# adafruit_rgblcdshield.net
KiCad netlist of a schematic drawn in EAGLE
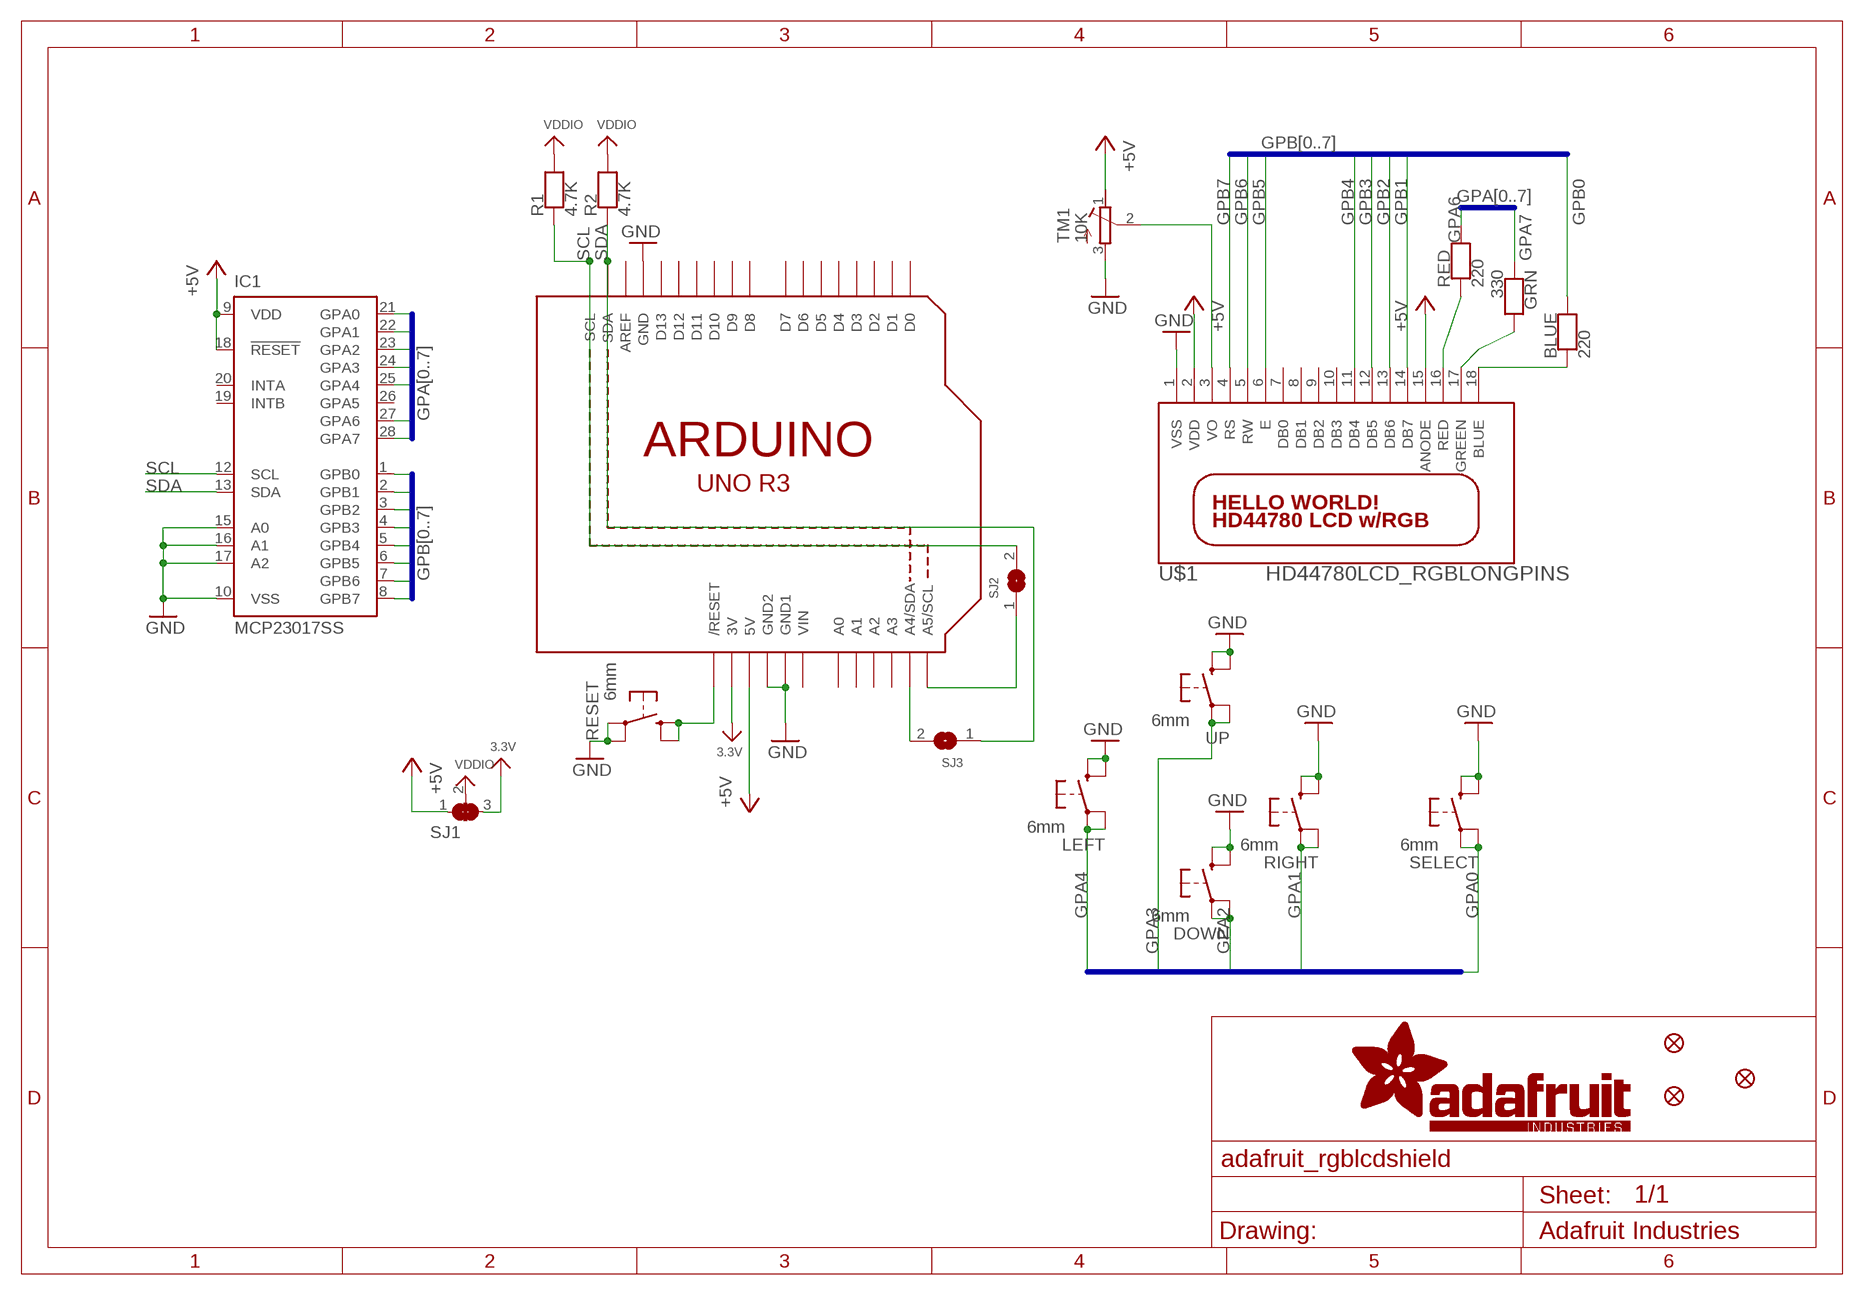
[diagram p0: schematic, sheet 1]

(export (version "E")
  (design (tool "Eeschema 10.0.6"))
  (components
    (comp (ref "BLUE")
      (value "220")
      (footprint "eagle-import:0805-NO")
      (libsource (lib "eagle-import") (part "RESISTOR0805_NOOUTLINE"))
    )
    (comp (ref "DOWN")
      (value "6mm")
      (footprint "eagle-import:6MMX6MM_TACTILE_SMT")
      (libsource (lib "eagle-import") (part "SWITCH_TACT_SMT_6MM"))
    )
    (comp (ref "FID1")
      (value "FIDUCIAL_1MM")
      (footprint "eagle-import:FIDUCIAL_1MM")
      (libsource (lib "eagle-import") (part "FIDUCIAL_1MM"))
    )
    (comp (ref "FID2")
      (value "FIDUCIAL_1MM")
      (footprint "eagle-import:FIDUCIAL_1MM")
      (libsource (lib "eagle-import") (part "FIDUCIAL_1MM"))
    )
    (comp (ref "FID3")
      (value "FIDUCIAL_1MM")
      (footprint "eagle-import:FIDUCIAL_1MM")
      (libsource (lib "eagle-import") (part "FIDUCIAL_1MM"))
    )
    (comp (ref "GRN")
      (value "330")
      (footprint "eagle-import:0805-NO")
      (libsource (lib "eagle-import") (part "RESISTOR0805_NOOUTLINE"))
    )
    (comp (ref "IC1")
      (value "MCP23017SS")
      (footprint "eagle-import:SSOP28")
      (libsource (lib "eagle-import") (part "MCP23017SS"))
    )
    (comp (ref "LEFT")
      (value "6mm")
      (footprint "eagle-import:6MMX6MM_TACTILE_SMT")
      (libsource (lib "eagle-import") (part "SWITCH_TACT_SMT_6MM"))
    )
    (comp (ref "R1")
      (value "4.7K")
      (footprint "eagle-import:0805-NO")
      (libsource (lib "eagle-import") (part "RESISTOR0805_NOOUTLINE"))
    )
    (comp (ref "R2")
      (value "4.7K")
      (footprint "eagle-import:0805-NO")
      (libsource (lib "eagle-import") (part "RESISTOR0805_NOOUTLINE"))
    )
    (comp (ref "RED")
      (value "220")
      (footprint "eagle-import:0805-NO")
      (libsource (lib "eagle-import") (part "RESISTOR0805_NOOUTLINE"))
    )
    (comp (ref "RESET")
      (value "6mm")
      (footprint "eagle-import:6MMX6MM_TACTILE_SMT")
      (libsource (lib "eagle-import") (part "SWITCH_TACT_SMT_6MM"))
    )
    (comp (ref "RIGHT")
      (value "6mm")
      (footprint "eagle-import:6MMX6MM_TACTILE_SMT")
      (libsource (lib "eagle-import") (part "SWITCH_TACT_SMT_6MM"))
    )
    (comp (ref "SELECT")
      (value "6mm")
      (footprint "eagle-import:6MMX6MM_TACTILE_SMT")
      (libsource (lib "eagle-import") (part "SWITCH_TACT_SMT_6MM"))
    )
    (comp (ref "SJ1")
      (value "SOLDERJUMPER_2WAY")
      (footprint "eagle-import:SOLDERJUMPER_2WAY_OPEN_NOPASTE")
      (libsource (lib "eagle-import") (part "SOLDERJUMPER_2WAY"))
    )
    (comp (ref "SJ2")
      (value "SOLDERJUMPER")
      (footprint "eagle-import:SOLDERJUMPER_ARROW_NOPASTE")
      (libsource (lib "eagle-import") (part "SOLDERJUMPER"))
    )
    (comp (ref "SJ3")
      (value "SOLDERJUMPER")
      (footprint "eagle-import:SOLDERJUMPER_ARROW_NOPASTE")
      (libsource (lib "eagle-import") (part "SOLDERJUMPER"))
    )
    (comp (ref "TM1")
      (value "10K")
      (footprint "eagle-import:RTRIM3314J")
      (libsource (lib "eagle-import") (part "R-TRIMM3314J"))
    )
    (comp (ref "U$1")
      (value "HD44780LCD_RGBLONGPINS")
      (footprint "eagle-import:LCD1602-RGB")
      (libsource (lib "eagle-import") (part "HD44780LCD_RGBLONGPINS"))
    )
    (comp (ref "U1")
      (value "ARDUINOR3-NOIOREF-NOTEXT")
      (footprint "eagle-import:ARDUINOR3-NOTEXT-NOIOREF")
      (libsource (lib "eagle-import") (part "ARDUINOR3-NOIOREF-NOTEXT"))
    )
    (comp (ref "UP")
      (value "6mm")
      (footprint "eagle-import:6MMX6MM_TACTILE_SMT")
      (libsource (lib "eagle-import") (part "SWITCH_TACT_SMT_6MM"))
    )
  )
  (nets
    (net (code "2") (name "+5V") (class "Default")
      (node (ref "IC1") (pin "18") (pinfunction "~{RESET}_18") (pintype "input"))
      (node (ref "IC1") (pin "9") (pinfunction "VDD_9") (pintype "power_in"))
      (node (ref "SJ1") (pin "1") (pinfunction "1_1") (pintype "passive"))
      (node (ref "TM1") (pin "1") (pinfunction "E_1") (pintype "passive"))
      (node (ref "U$1") (pin "15") (pinfunction "ANODE_15") (pintype "input"))
      (node (ref "U$1") (pin "2") (pinfunction "VDD_2") (pintype "power_in"))
      (node (ref "U1") (pin "5V") (pinfunction "5V_5V") (pintype "power_in"))
    )
    (net (code "3") (name "/GPA0") (class "Default")
      (node (ref "IC1") (pin "21") (pinfunction "GPA0_21") (pintype "bidirectional"))
      (node (ref "SELECT") (pin "A") (pinfunction "P_A") (pintype "passive"))
      (node (ref "SELECT") (pin "A'") (pinfunction "P1_A'") (pintype "passive"))
    )
    (net (code "4") (name "/GPA1") (class "Default")
      (node (ref "IC1") (pin "22") (pinfunction "GPA1_22") (pintype "bidirectional"))
      (node (ref "RIGHT") (pin "A") (pinfunction "P_A") (pintype "passive"))
      (node (ref "RIGHT") (pin "A'") (pinfunction "P1_A'") (pintype "passive"))
    )
    (net (code "5") (name "/GPA2") (class "Default")
      (node (ref "DOWN") (pin "A") (pinfunction "P_A") (pintype "passive"))
      (node (ref "DOWN") (pin "A'") (pinfunction "P1_A'") (pintype "passive"))
      (node (ref "IC1") (pin "23") (pinfunction "GPA2_23") (pintype "bidirectional"))
    )
    (net (code "6") (name "/GPA3") (class "Default")
      (node (ref "IC1") (pin "24") (pinfunction "GPA3_24") (pintype "bidirectional"))
      (node (ref "UP") (pin "A") (pinfunction "P_A") (pintype "passive"))
      (node (ref "UP") (pin "A'") (pinfunction "P1_A'") (pintype "passive"))
    )
    (net (code "7") (name "/GPA4") (class "Default")
      (node (ref "IC1") (pin "25") (pinfunction "GPA4_25") (pintype "bidirectional"))
      (node (ref "LEFT") (pin "A") (pinfunction "P_A") (pintype "passive"))
      (node (ref "LEFT") (pin "A'") (pinfunction "P1_A'") (pintype "passive"))
    )
    (net (code "8") (name "/GPA6") (class "Default")
      (node (ref "IC1") (pin "27") (pinfunction "GPA6_27") (pintype "bidirectional"))
      (node (ref "RED") (pin "2") (pinfunction "2_2") (pintype "passive"))
    )
    (net (code "9") (name "/GPA7") (class "Default")
      (node (ref "GRN") (pin "1") (pinfunction "1_1") (pintype "passive"))
      (node (ref "IC1") (pin "28") (pinfunction "GPA7_28") (pintype "bidirectional"))
    )
    (net (code "11") (name "/GPB0") (class "Default")
      (node (ref "BLUE") (pin "2") (pinfunction "2_2") (pintype "passive"))
      (node (ref "IC1") (pin "1") (pinfunction "GPB0_1") (pintype "bidirectional"))
    )
    (net (code "12") (name "/GPB1") (class "Default")
      (node (ref "IC1") (pin "2") (pinfunction "GPB1_2") (pintype "bidirectional"))
      (node (ref "U$1") (pin "14") (pinfunction "DB7_14") (pintype "bidirectional"))
    )
    (net (code "13") (name "/GPB2") (class "Default")
      (node (ref "IC1") (pin "3") (pinfunction "GPB2_3") (pintype "bidirectional"))
      (node (ref "U$1") (pin "13") (pinfunction "DB6_13") (pintype "bidirectional"))
    )
    (net (code "14") (name "/GPB3") (class "Default")
      (node (ref "IC1") (pin "4") (pinfunction "GPB3_4") (pintype "bidirectional"))
      (node (ref "U$1") (pin "12") (pinfunction "DB5_12") (pintype "bidirectional"))
    )
    (net (code "15") (name "/GPB4") (class "Default")
      (node (ref "IC1") (pin "5") (pinfunction "GPB4_5") (pintype "bidirectional"))
      (node (ref "U$1") (pin "11") (pinfunction "DB4_11") (pintype "bidirectional"))
    )
    (net (code "16") (name "/GPB5") (class "Default")
      (node (ref "IC1") (pin "6") (pinfunction "GPB5_6") (pintype "bidirectional"))
      (node (ref "U$1") (pin "6") (pinfunction "E_6") (pintype "input"))
    )
    (net (code "17") (name "/GPB6") (class "Default")
      (node (ref "IC1") (pin "7") (pinfunction "GPB6_7") (pintype "bidirectional"))
      (node (ref "U$1") (pin "5") (pinfunction "RW_5") (pintype "input"))
    )
    (net (code "18") (name "/GPB7") (class "Default")
      (node (ref "IC1") (pin "8") (pinfunction "GPB7_8") (pintype "bidirectional"))
      (node (ref "U$1") (pin "4") (pinfunction "RS_4") (pintype "input"))
    )
    (net (code "20") (name "/SCL") (class "Default")
      (node (ref "IC1") (pin "12") (pinfunction "SCL_12") (pintype "input"))
      (node (ref "R1") (pin "1") (pinfunction "1_1") (pintype "passive"))
      (node (ref "SJ2") (pin "2") (pinfunction "2_2") (pintype "passive"))
      (node (ref "U1") (pin "SCL") (pinfunction "SCL_SCL") (pintype "bidirectional"))
    )
    (net (code "21") (name "/SDA") (class "Default")
      (node (ref "IC1") (pin "13") (pinfunction "SDA_13") (pintype "bidirectional"))
      (node (ref "R2") (pin "1") (pinfunction "1_1") (pintype "passive"))
      (node (ref "SJ3") (pin "1") (pinfunction "1_1") (pintype "passive"))
      (node (ref "U1") (pin "SDA") (pinfunction "SDA_SDA") (pintype "bidirectional"))
    )
    (net (code "22") (name "/VIN") (class "Default")
      (node (ref "U1") (pin "VIN") (pinfunction "VIN_VIN") (pintype "power_in"))
    )
    (net (code "23") (name "3.3V") (class "Default")
      (node (ref "SJ1") (pin "3") (pinfunction "3_3") (pintype "passive"))
      (node (ref "U1") (pin "3V") (pinfunction "3V_3V") (pintype "power_in"))
    )
    (net (code "24") (name "GND") (class "Default")
      (node (ref "DOWN") (pin "B") (pinfunction "S_B") (pintype "passive"))
      (node (ref "DOWN") (pin "B'") (pinfunction "S1_B'") (pintype "passive"))
      (node (ref "IC1") (pin "10") (pinfunction "VSS_10") (pintype "power_in"))
      (node (ref "IC1") (pin "15") (pinfunction "A0_15") (pintype "input"))
      (node (ref "IC1") (pin "16") (pinfunction "A1_16") (pintype "input"))
      (node (ref "IC1") (pin "17") (pinfunction "A2_17") (pintype "input"))
      (node (ref "LEFT") (pin "B") (pinfunction "S_B") (pintype "passive"))
      (node (ref "LEFT") (pin "B'") (pinfunction "S1_B'") (pintype "passive"))
      (node (ref "RESET") (pin "A") (pinfunction "P_A") (pintype "passive"))
      (node (ref "RESET") (pin "A'") (pinfunction "P1_A'") (pintype "passive"))
      (node (ref "RIGHT") (pin "B") (pinfunction "S_B") (pintype "passive"))
      (node (ref "RIGHT") (pin "B'") (pinfunction "S1_B'") (pintype "passive"))
      (node (ref "SELECT") (pin "B") (pinfunction "S_B") (pintype "passive"))
      (node (ref "SELECT") (pin "B'") (pinfunction "S1_B'") (pintype "passive"))
      (node (ref "TM1") (pin "3") (pinfunction "A_3") (pintype "passive"))
      (node (ref "U$1") (pin "1") (pinfunction "VSS_1") (pintype "power_in"))
      (node (ref "U1") (pin "GND") (pinfunction "GND_GND") (pintype "power_in"))
      (node (ref "U1") (pin "GND1") (pinfunction "GND1_GND1") (pintype "power_in"))
      (node (ref "U1") (pin "GND2") (pinfunction "GND2_GND2") (pintype "power_in"))
      (node (ref "UP") (pin "B") (pinfunction "S_B") (pintype "passive"))
      (node (ref "UP") (pin "B'") (pinfunction "S1_B'") (pintype "passive"))
    )
    (net (code "25") (name "Net-(RESET-S)") (class "Default")
      (node (ref "RESET") (pin "B") (pinfunction "S_B") (pintype "passive"))
      (node (ref "RESET") (pin "B'") (pinfunction "S1_B'") (pintype "passive"))
      (node (ref "U1") (pin "RESET") (pinfunction "/RESET_RESET") (pintype "bidirectional"))
    )
    (net (code "26") (name "Net-(TM1-S)") (class "Default")
      (node (ref "TM1") (pin "2") (pinfunction "S_2") (pintype "passive"))
      (node (ref "U$1") (pin "3") (pinfunction "VO_3") (pintype "input"))
    )
    (net (code "27") (name "Net-(U$1-BLUE)") (class "Default")
      (node (ref "BLUE") (pin "1") (pinfunction "1_1") (pintype "passive"))
      (node (ref "U$1") (pin "18") (pinfunction "BLUE_18") (pintype "input"))
    )
    (net (code "28") (name "Net-(U$1-GREEN)") (class "Default")
      (node (ref "GRN") (pin "2") (pinfunction "2_2") (pintype "passive"))
      (node (ref "U$1") (pin "17") (pinfunction "GREEN_17") (pintype "input"))
    )
    (net (code "29") (name "Net-(U$1-RED)") (class "Default")
      (node (ref "RED") (pin "1") (pinfunction "1_1") (pintype "passive"))
      (node (ref "U$1") (pin "16") (pinfunction "RED_16") (pintype "input"))
    )
    (net (code "30") (name "Net-(U1-A4{slash}SDA)") (class "Default")
      (node (ref "SJ3") (pin "2") (pinfunction "2_2") (pintype "passive"))
      (node (ref "U1") (pin "A4") (pinfunction "A4/SDA_A4") (pintype "bidirectional"))
    )
    (net (code "31") (name "Net-(U1-A5{slash}SCL)") (class "Default")
      (node (ref "SJ2") (pin "1") (pinfunction "1_1") (pintype "passive"))
      (node (ref "U1") (pin "A5") (pinfunction "A5/SCL_A5") (pintype "bidirectional"))
    )
    (net (code "32") (name "VDDIO") (class "Default")
      (node (ref "R1") (pin "2") (pinfunction "2_2") (pintype "passive"))
      (node (ref "R2") (pin "2") (pinfunction "2_2") (pintype "passive"))
      (node (ref "SJ1") (pin "2") (pinfunction "2_2") (pintype "passive"))
    )
    (net (code "33") (name "unconnected-(IC1-GPA5-Pad26)") (class "Default")
      (node (ref "IC1") (pin "26") (pinfunction "GPA5_26") (pintype "bidirectional"))
    )
    (net (code "34") (name "unconnected-(IC1-INTA-Pad20)") (class "Default")
      (node (ref "IC1") (pin "20") (pinfunction "INTA_20") (pintype "output"))
    )
    (net (code "35") (name "unconnected-(IC1-INTB-Pad19)") (class "Default")
      (node (ref "IC1") (pin "19") (pinfunction "INTB_19") (pintype "output"))
    )
    (net (code "36") (name "unconnected-(U$1-DB0-Pad7)") (class "Default")
      (node (ref "U$1") (pin "7") (pinfunction "DB0_7") (pintype "bidirectional"))
    )
    (net (code "37") (name "unconnected-(U$1-DB1-Pad8)") (class "Default")
      (node (ref "U$1") (pin "8") (pinfunction "DB1_8") (pintype "bidirectional"))
    )
    (net (code "38") (name "unconnected-(U$1-DB2-Pad9)") (class "Default")
      (node (ref "U$1") (pin "9") (pinfunction "DB2_9") (pintype "bidirectional"))
    )
    (net (code "39") (name "unconnected-(U$1-DB3-Pad10)") (class "Default")
      (node (ref "U$1") (pin "10") (pinfunction "DB3_10") (pintype "bidirectional"))
    )
    (net (code "40") (name "unconnected-(U1-PadA0)") (class "Default")
      (node (ref "U1") (pin "A0") (pinfunction "A0_A0") (pintype "bidirectional"))
    )
    (net (code "41") (name "unconnected-(U1-PadA1)") (class "Default")
      (node (ref "U1") (pin "A1") (pinfunction "A1_A1") (pintype "bidirectional"))
    )
    (net (code "42") (name "unconnected-(U1-PadA2)") (class "Default")
      (node (ref "U1") (pin "A2") (pinfunction "A2_A2") (pintype "bidirectional"))
    )
    (net (code "43") (name "unconnected-(U1-PadA3)") (class "Default")
      (node (ref "U1") (pin "A3") (pinfunction "A3_A3") (pintype "bidirectional"))
    )
    (net (code "44") (name "unconnected-(U1-PadAREF)") (class "Default")
      (node (ref "U1") (pin "AREF") (pinfunction "AREF_AREF") (pintype "bidirectional"))
    )
    (net (code "45") (name "unconnected-(U1-PadD0)") (class "Default")
      (node (ref "U1") (pin "D0") (pinfunction "D0_D0") (pintype "bidirectional"))
    )
    (net (code "46") (name "unconnected-(U1-PadD1)") (class "Default")
      (node (ref "U1") (pin "D1") (pinfunction "D1_D1") (pintype "bidirectional"))
    )
    (net (code "47") (name "unconnected-(U1-PadD2)") (class "Default")
      (node (ref "U1") (pin "D2") (pinfunction "D2_D2") (pintype "bidirectional"))
    )
    (net (code "48") (name "unconnected-(U1-PadD3)") (class "Default")
      (node (ref "U1") (pin "D3") (pinfunction "D3_D3") (pintype "bidirectional"))
    )
    (net (code "49") (name "unconnected-(U1-PadD4)") (class "Default")
      (node (ref "U1") (pin "D4") (pinfunction "D4_D4") (pintype "bidirectional"))
    )
    (net (code "50") (name "unconnected-(U1-PadD5)") (class "Default")
      (node (ref "U1") (pin "D5") (pinfunction "D5_D5") (pintype "bidirectional"))
    )
    (net (code "51") (name "unconnected-(U1-PadD6)") (class "Default")
      (node (ref "U1") (pin "D6") (pinfunction "D6_D6") (pintype "bidirectional"))
    )
    (net (code "52") (name "unconnected-(U1-PadD7)") (class "Default")
      (node (ref "U1") (pin "D7") (pinfunction "D7_D7") (pintype "bidirectional"))
    )
    (net (code "53") (name "unconnected-(U1-PadD8)") (class "Default")
      (node (ref "U1") (pin "D8") (pinfunction "D8_D8") (pintype "bidirectional"))
    )
    (net (code "54") (name "unconnected-(U1-PadD9)") (class "Default")
      (node (ref "U1") (pin "D9") (pinfunction "D9_D9") (pintype "bidirectional"))
    )
    (net (code "55") (name "unconnected-(U1-PadD10)") (class "Default")
      (node (ref "U1") (pin "D10") (pinfunction "D10_D10") (pintype "bidirectional"))
    )
    (net (code "56") (name "unconnected-(U1-PadD11)") (class "Default")
      (node (ref "U1") (pin "D11") (pinfunction "D11_D11") (pintype "bidirectional"))
    )
    (net (code "57") (name "unconnected-(U1-PadD12)") (class "Default")
      (node (ref "U1") (pin "D12") (pinfunction "D12_D12") (pintype "bidirectional"))
    )
    (net (code "58") (name "unconnected-(U1-PadD13)") (class "Default")
      (node (ref "U1") (pin "D13") (pinfunction "D13_D13") (pintype "bidirectional"))
    )
  )
)
